# 433.net
KiCad netlist of a schematic drawn in EasyEDA Pro
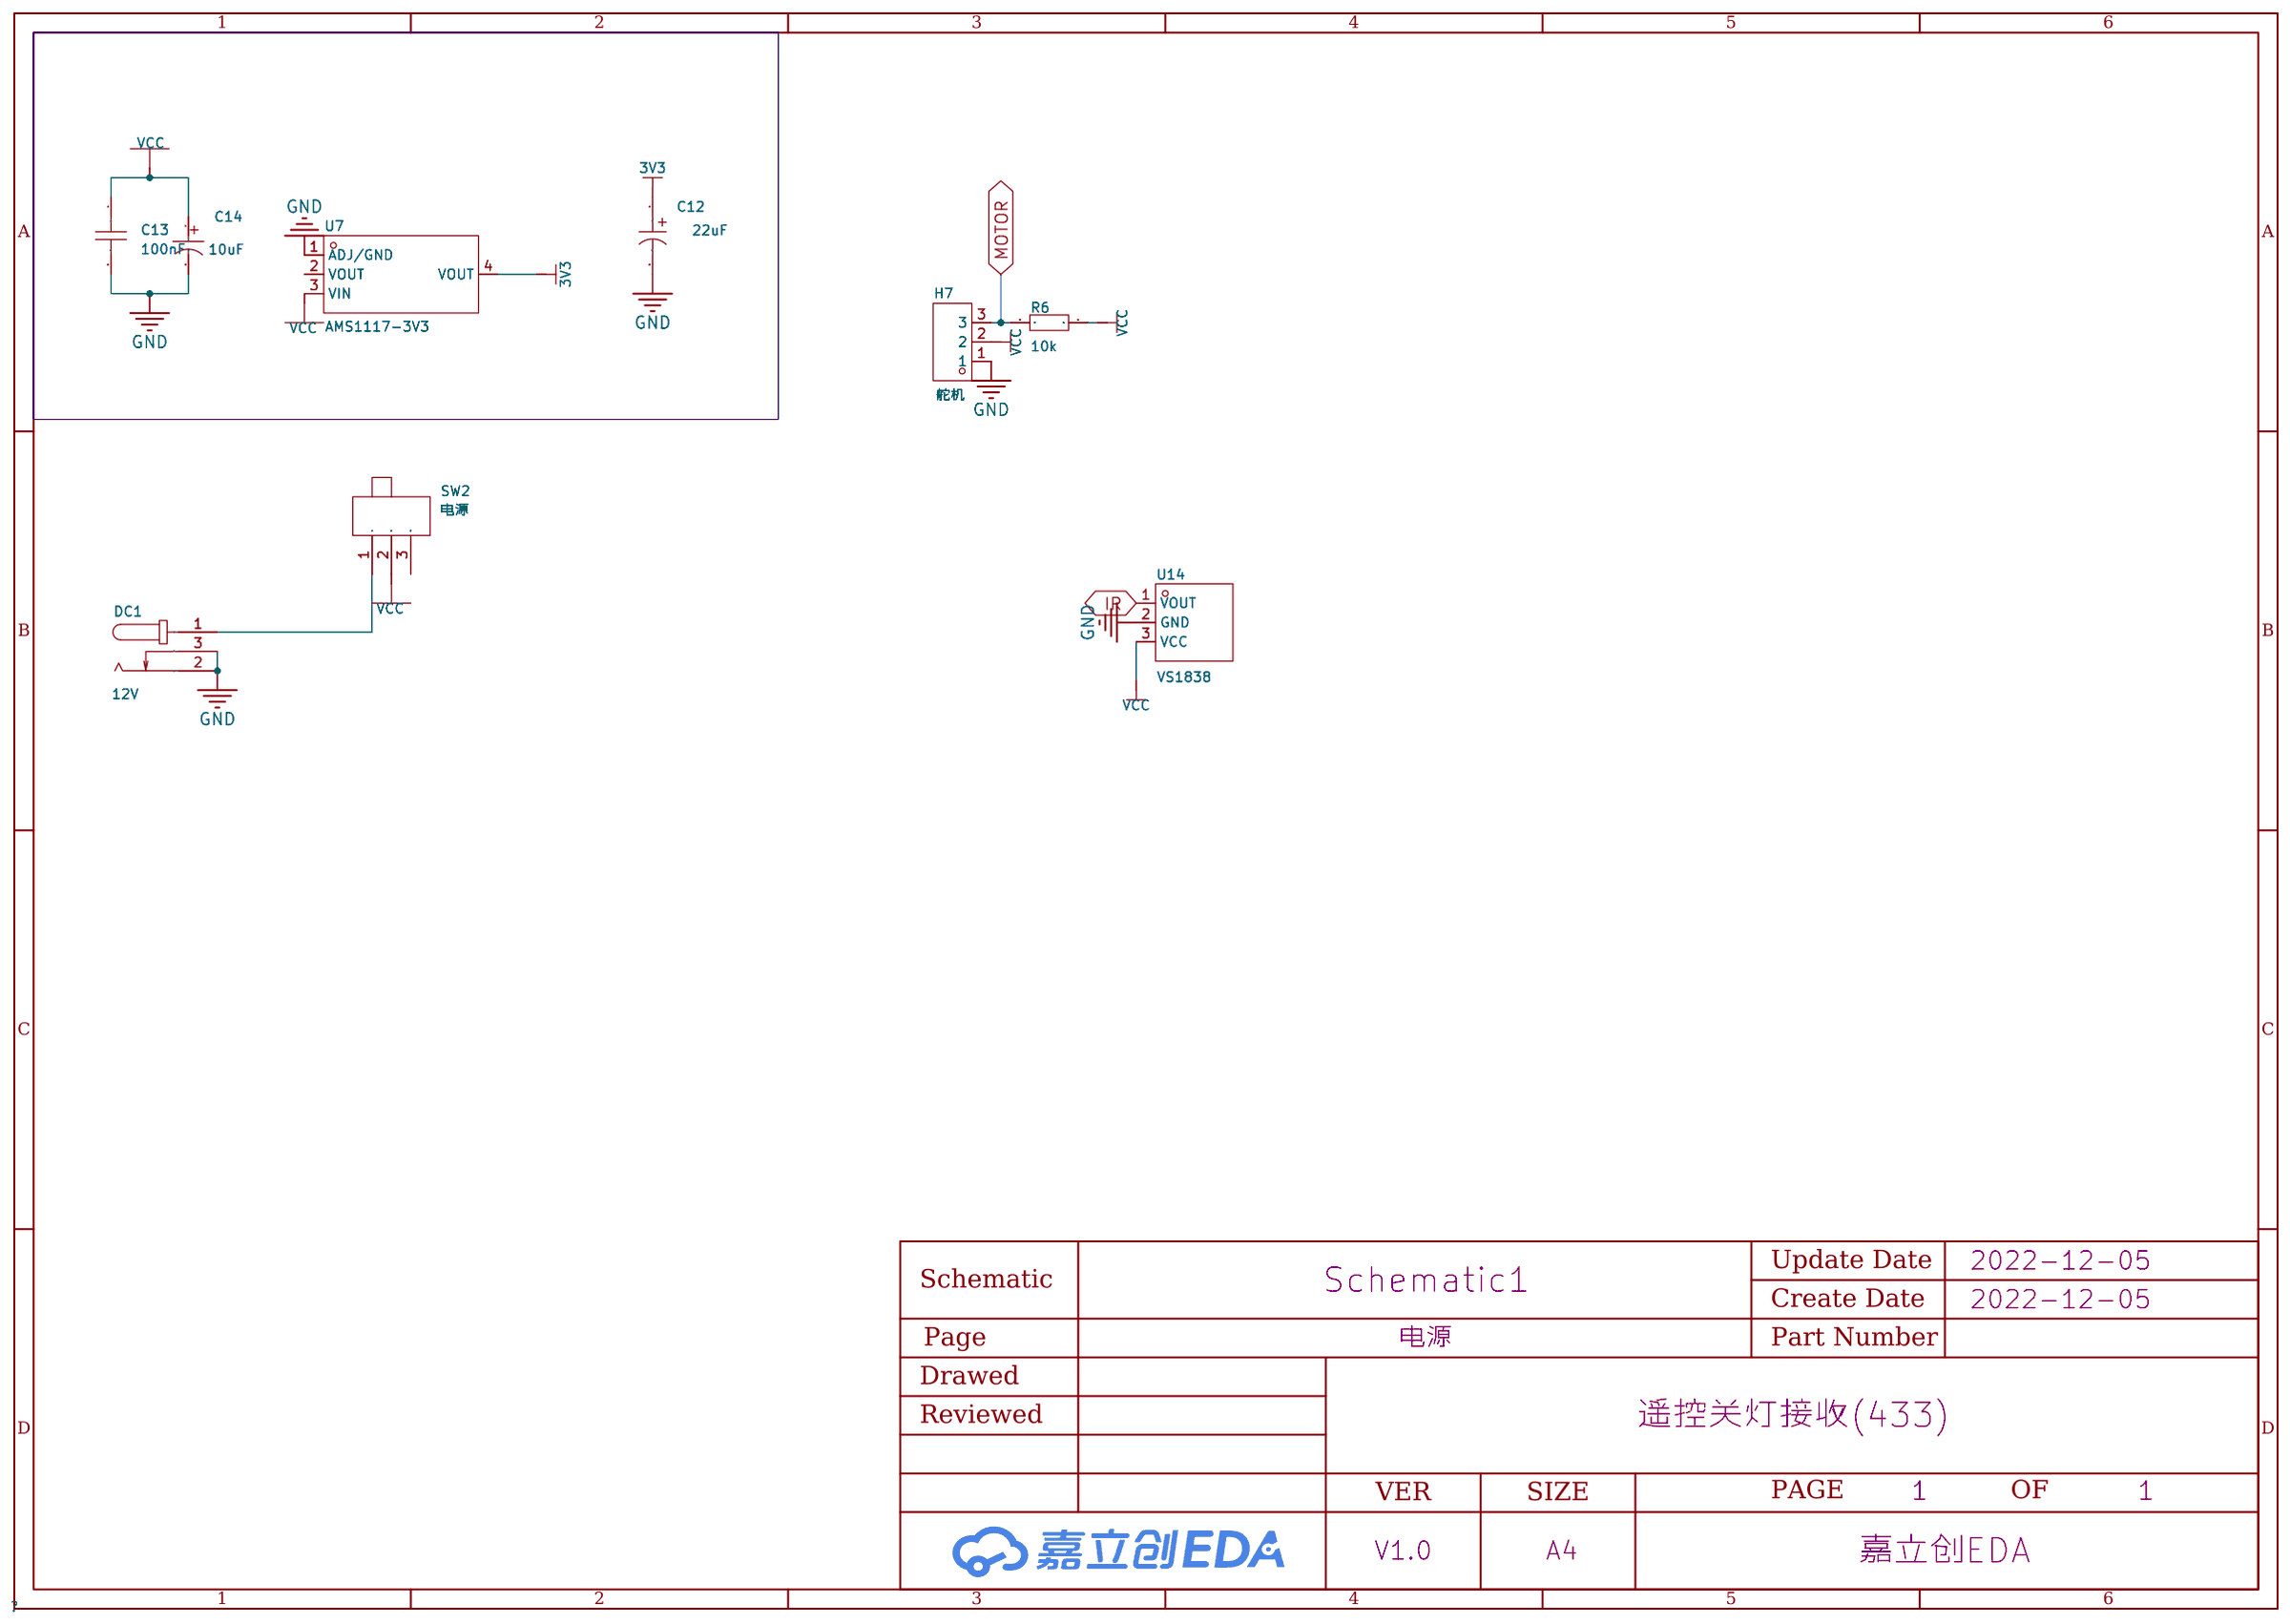
[diagram p0: 电源]
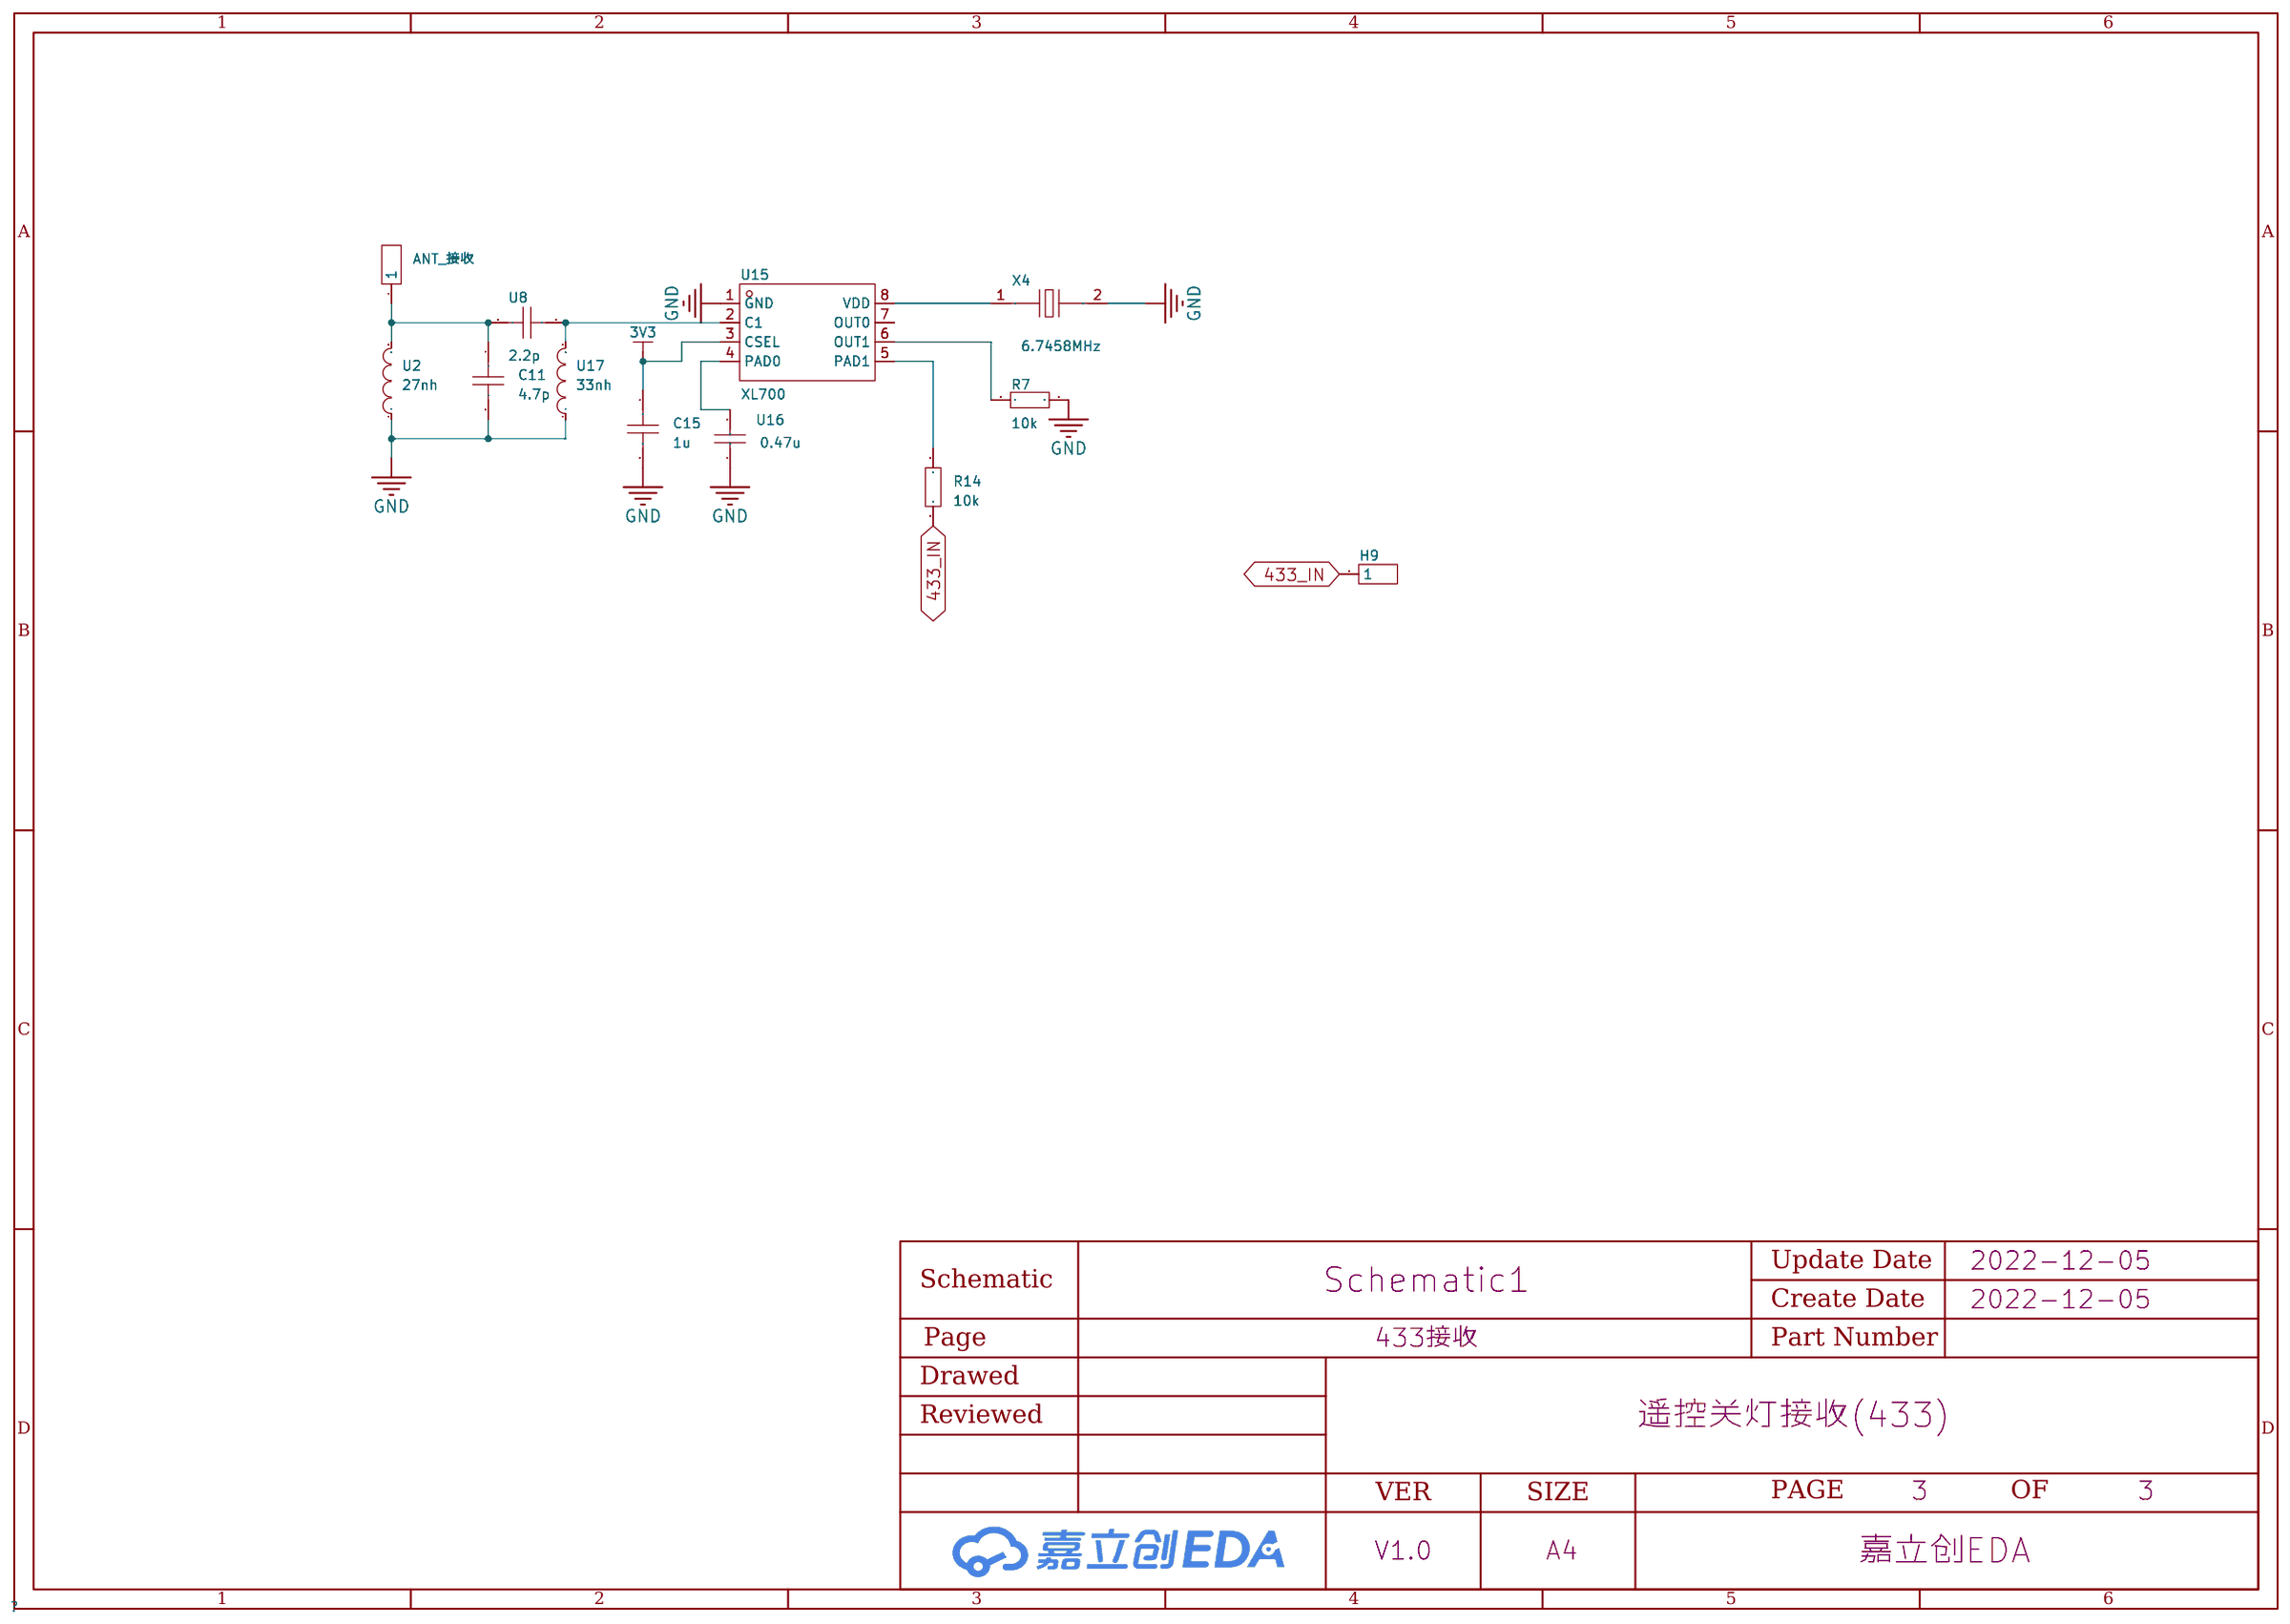
[diagram p1: 433接收]
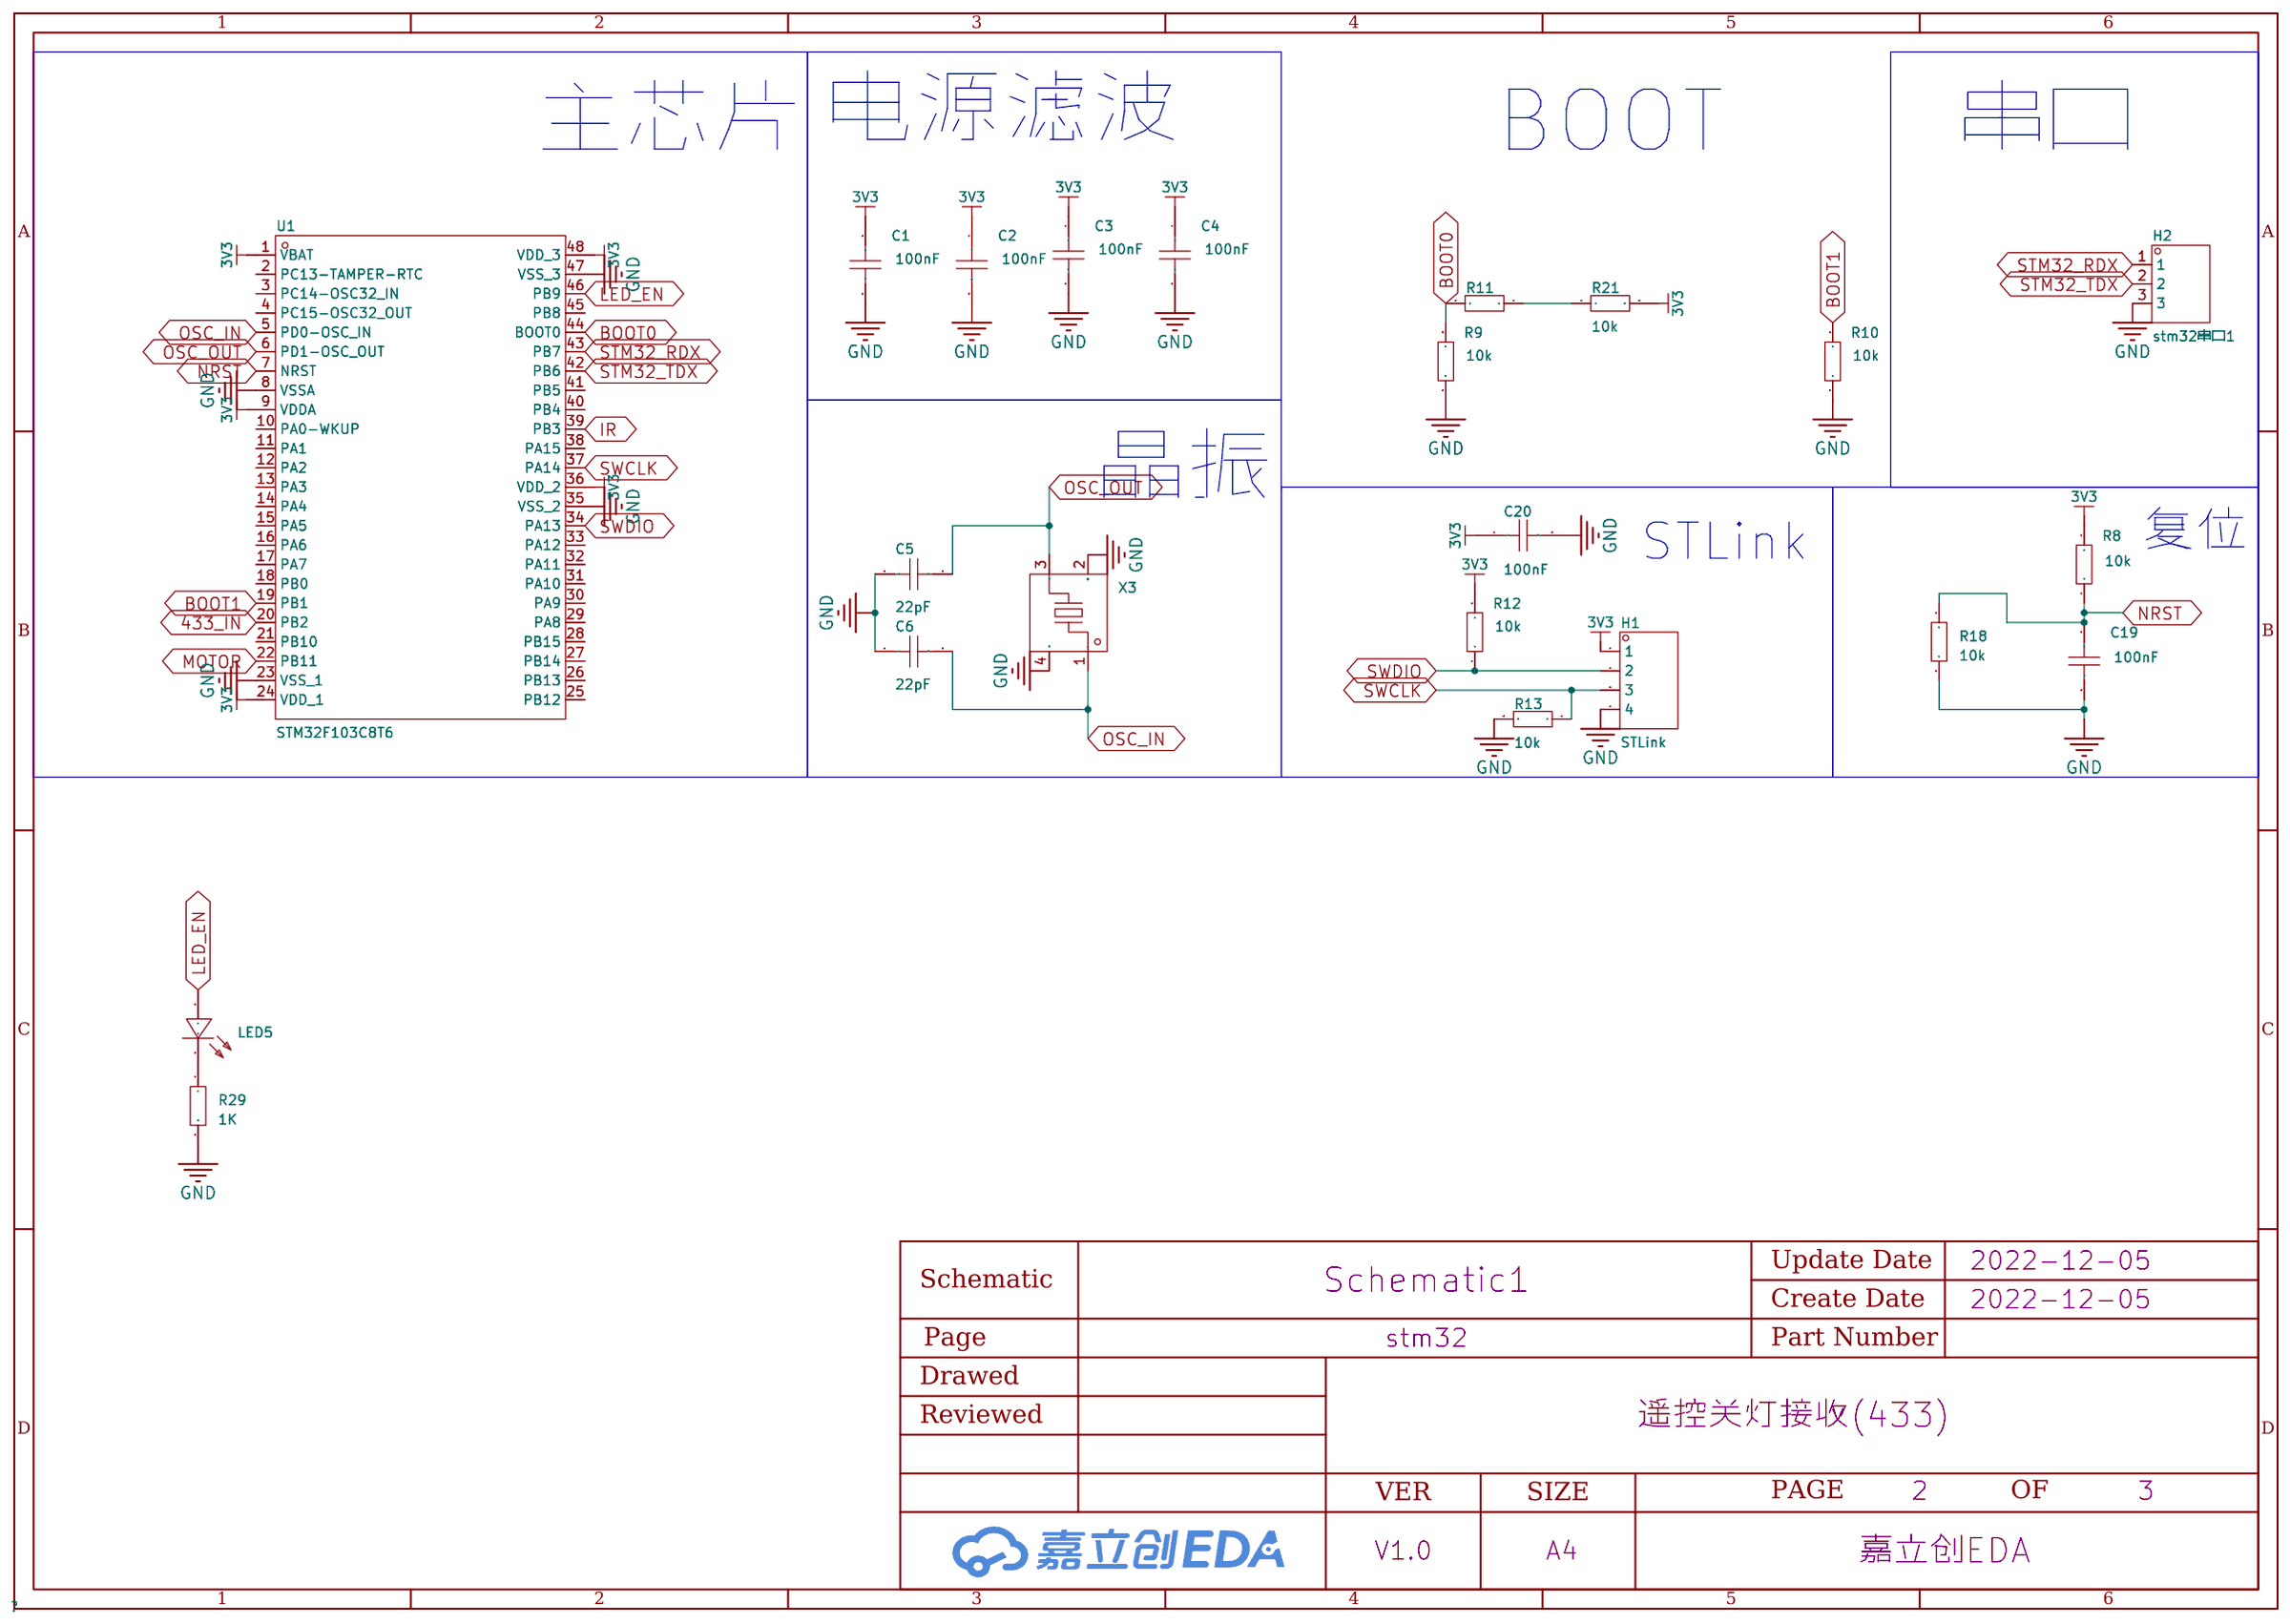
[diagram p2: stm32]

(export (version "E")
  (design (tool "Eeschema 10.0.6"))
  (components
    (comp (ref "C12")
      (value "22uF")
      (footprint "easyedapro:CAP-TH_BD5.0-P2.00-D0.6-FD")
      (fields
        (field (name "Manufacturer Part") "LW220M0500511PV2-D5")
        (field (name "Manufacturer") "UNITED(怡德)")
      )
      (libsource (lib "easyedapro") (part "LW220M0500511PV2-D5"))
    )
    (comp (ref "C13")
      (value "100nF")
      (footprint "easyedapro:C0805")
      (fields (field (name "Manufacturer Part") "0805"))
      (libsource (lib "easyedapro") (part "0805_C9900012713"))
    )
    (comp (ref "C14")
      (value "10uF")
      (footprint "easyedapro:CAP-TH_BD5.0-P2.00-D0.8-FD")
      (fields
        (field (name "Manufacturer Part") "KM106M025D11RR0VH2FP0")
        (field (name "Manufacturer") "CX(承兴)")
      )
      (libsource (lib "easyedapro") (part "10uF 25V 5*11"))
    )
    (comp (ref "DC1")
      (value "12V")
      (footprint "easyedapro:DC-IN-TH_DC005-T20")
      (description "连接器类型:DC电源插座;安装方式:弯插;触点内径:-;触点外径:6.3mm;额定电流:3A;额定电压:30V;工作温度范围:-10~+60;")
      (fields (field (name "Manufacturer Part") "DC005-T20") (field (name "Manufacturer") "SOFNG(硕方)"))
      (libsource (lib "easyedapro") (part "DC005-2.0MM"))
    )
    (comp (ref "H7")
      (value "舵机")
      (footprint "easyedapro:HDR-TH_3P-P2.54-V-F")
      (libsource (lib "easyedapro") (part "PM254V-11-03-H85"))
    )
    (comp (ref "R6")
      (value "10k")
      (footprint "easyedapro:R0805")
      (fields (field (name "Manufacturer Part") "0805"))
      (libsource (lib "easyedapro") (part "0805"))
    )
    (comp (ref "SW2")
      (value "电源")
      (footprint "easyedapro:SW-TH_MK-12D18-G040")
      (fields (field (name "Manufacturer Part") "MK-12D18-G020") (field (name "Manufacturer") "G-Switch(品赞)"))
      (libsource (lib "easyedapro") (part "MK-12D18-G020"))
    )
    (comp (ref "U7")
      (value "AMS1117-3V3")
      (footprint "easyedapro:SOT-223-3_L6.7-W3.7-P2.30-LS7.0-BR")
      (description "静态电流(Iq):-;输出类型:固定;最大输入电压:18V;输出电压(可调):-;压降(max):1.5V @ 1A;输出电压(固定):5V;")
      (fields (field (name "Manufacturer Part") "AMS1117-5.0") (field (name "Manufacturer") "Slkor(萨科微)"))
      (libsource (lib "easyedapro") (part "AMS1117-5.0_C473812"))
    )
    (comp (ref "U14")
      (value "VS1838")
      (footprint "easyedapro:OPTO-TH_3P-L7.0-W5.6-P2.54-L")
      (fields (field (name "Manufacturer Part") "DY-IRM-AC01-AN") (field (name "Manufacturer") "TONYU(东裕)"))
      (libsource (lib "easyedapro") (part "DY-IRM-AC01-AN"))
    )
    (comp (ref "ANT_接收")
      (value "~")
      (footprint "easyedapro:HDR-TH_1P-V-M_XKB_X4611WV-01I-C28D40")
      (libsource (lib "easyedapro") (part "HDR_1x1"))
    )
    (comp (ref "C11")
      (value "4.7p")
      (footprint "easyedapro:C0805")
      (fields (field (name "Manufacturer Part") "0805"))
      (libsource (lib "easyedapro") (part "0805_C9900012713"))
    )
    (comp (ref "C15")
      (value "1u")
      (footprint "easyedapro:C0805")
      (fields (field (name "Manufacturer Part") "0805"))
      (libsource (lib "easyedapro") (part "0805_C9900012713"))
    )
    (comp (ref "H9")
      (value "~")
      (footprint "easyedapro:HDR-TH_1P-V-M_XKB_X4611WV-01I-C28D40")
      (libsource (lib "easyedapro") (part "HDR_1x1"))
    )
    (comp (ref "R7")
      (value "10k")
      (footprint "easyedapro:R0805")
      (fields (field (name "Manufacturer Part") "0805"))
      (libsource (lib "easyedapro") (part "0805"))
    )
    (comp (ref "R14")
      (value "10k")
      (footprint "easyedapro:R0805")
      (fields (field (name "Manufacturer Part") "0805"))
      (libsource (lib "easyedapro") (part "0805"))
    )
    (comp (ref "U2")
      (value "27nh")
      (footprint "easyedapro:L0603")
      (fields (field (name "Manufacturer Part") "1.3nH±10%"))
      (libsource (lib "easyedapro") (part "1.3NH±10%"))
    )
    (comp (ref "U8")
      (value "2.2p")
      (footprint "easyedapro:C0603")
      (fields (field (name "Manufacturer Part") "104P"))
      (libsource (lib "easyedapro") (part "104P"))
    )
    (comp (ref "U15")
      (value "XL700")
      (footprint "easyedapro:SOP-8_L4.9-W3.9-P1.27-LS6.0-BL")
      (fields (field (name "Manufacturer Part") "XW02E SOP8") (field (name "Manufacturer") "Sam&wing(芯网)"))
      (libsource (lib "easyedapro") (part "XW02E SOP8"))
    )
    (comp (ref "U16")
      (value "0.47u")
      (footprint "easyedapro:C0402")
      (fields (field (name "Manufacturer Part") "16p"))
      (libsource (lib "easyedapro") (part "16P"))
    )
    (comp (ref "U17")
      (value "33nh")
      (footprint "easyedapro:L0603")
      (fields (field (name "Manufacturer Part") "1.3nH±10%"))
      (libsource (lib "easyedapro") (part "1.3NH±10%"))
    )
    (comp (ref "X4")
      (value "6.7458MHz")
      (footprint "easyedapro:OSC-SMD_2P-L11.4-W4.7-LS12.3")
      (description "晶振类型:-;频率:-;负载电容:-;工作温度:-;")
      (fields
        (field (name "Manufacturer Part") "49SMD-4MHZ-15PF-20PPM")
        (field (name "Manufacturer") "TKD(泰晶)")
      )
      (libsource (lib "easyedapro") (part "49SMD-4MHZ-15PF-20PPM"))
    )
    (comp (ref "C1")
      (value "100nF")
      (fields (field (name "Manufacturer Part") "0805"))
      (libsource (lib "easyedapro") (part "0805_C9900012713"))
    )
    (comp (ref "C2")
      (value "100nF")
      (fields (field (name "Manufacturer Part") "0805"))
      (libsource (lib "easyedapro") (part "0805_C9900012713"))
    )
    (comp (ref "C3")
      (value "100nF")
      (fields (field (name "Manufacturer Part") "0805"))
      (libsource (lib "easyedapro") (part "0805_C9900012713"))
    )
    (comp (ref "C4")
      (value "100nF")
      (fields (field (name "Manufacturer Part") "0805"))
      (libsource (lib "easyedapro") (part "0805_C9900012713"))
    )
    (comp (ref "C5")
      (value "22pF")
      (fields (field (name "Manufacturer Part") "0805"))
      (libsource (lib "easyedapro") (part "0805_C9900012713"))
    )
    (comp (ref "C6")
      (value "22pF")
      (fields (field (name "Manufacturer Part") "0805"))
      (libsource (lib "easyedapro") (part "0805_C9900012713"))
    )
    (comp (ref "C19")
      (value "100nF")
      (footprint "easyedapro:C0805")
      (fields (field (name "Manufacturer Part") "0805"))
      (libsource (lib "easyedapro") (part "0805_C9900012713"))
    )
    (comp (ref "C20")
      (value "100nF")
      (footprint "easyedapro:C0805")
      (fields (field (name "Manufacturer Part") "0805"))
      (libsource (lib "easyedapro") (part "0805_C9900012713"))
    )
    (comp (ref "H1")
      (value "STLink")
      (footprint "easyedapro:HDR-TH_4P-P2.54-V-M")
      (fields (field (name "Manufacturer Part") "B-2100S04P-A110") (field (name "Manufacturer") "Ckmtw(灿科盟)"))
      (libsource (lib "easyedapro") (part "Header-Male-2.54_1x4"))
    )
    (comp (ref "H2")
      (value "stm32串口1")
      (footprint "easyedapro:HDR-TH_3P-P2.54-V-M-1")
      (fields (field (name "Manufacturer Part") "77311-102-03LF") (field (name "Manufacturer") "Amphenol"))
      (libsource (lib "easyedapro") (part "77311-102-03LF"))
    )
    (comp (ref "LED5")
      (value "~")
      (footprint "easyedapro:LED0805-R-RD")
      (description "发光颜色:翠绿;")
      (fields (field (name "Manufacturer Part") "NCD0805G1") (field (name "Manufacturer") "国星光电"))
      (libsource (lib "easyedapro") (part "FC-2012UGK-520D5"))
    )
    (comp (ref "R8")
      (value "10k")
      (footprint "easyedapro:R0805")
      (fields (field (name "Manufacturer Part") "0805"))
      (libsource (lib "easyedapro") (part "0805"))
    )
    (comp (ref "R9")
      (value "10k")
      (footprint "easyedapro:R0805")
      (fields (field (name "Manufacturer Part") "0805"))
      (libsource (lib "easyedapro") (part "0805"))
    )
    (comp (ref "R10")
      (value "10k")
      (footprint "easyedapro:R0805")
      (fields (field (name "Manufacturer Part") "0805"))
      (libsource (lib "easyedapro") (part "0805"))
    )
    (comp (ref "R11")
      (value "100R")
      (footprint "easyedapro:R0805")
      (fields (field (name "Manufacturer Part") "0805"))
      (libsource (lib "easyedapro") (part "0805"))
    )
    (comp (ref "R12")
      (value "10k")
      (footprint "easyedapro:R0805")
      (fields (field (name "Manufacturer Part") "0805"))
      (libsource (lib "easyedapro") (part "0805"))
    )
    (comp (ref "R13")
      (value "10k")
      (footprint "easyedapro:R0805")
      (fields (field (name "Manufacturer Part") "0805"))
      (libsource (lib "easyedapro") (part "0805"))
    )
    (comp (ref "R18")
      (value "10k")
      (footprint "easyedapro:R0805")
      (fields (field (name "Manufacturer Part") "0805"))
      (libsource (lib "easyedapro") (part "0805"))
    )
    (comp (ref "R21")
      (value "10k")
      (footprint "easyedapro:R0805")
      (fields (field (name "Manufacturer Part") "0805"))
      (libsource (lib "easyedapro") (part "0805"))
    )
    (comp (ref "R29")
      (value "1K")
      (footprint "easyedapro:R0805")
      (fields (field (name "Manufacturer Part") "0805"))
      (libsource (lib "easyedapro") (part "0805"))
    )
    (comp (ref "U1")
      (value "STM32F103C8T6")
      (footprint "easyedapro:LQFP-48_L7.0-W7.0-P0.50-LS9.0-BL")
      (description "CPU位数:32-Bit;ROM类型:FLASH;CPU内核:ARM® Cortex®-M3;主频（MAX):72MHz;工作电压:2V ~ 3.6V;")
      (fields (field (name "Manufacturer") "ST(意法半导体)"))
      (libsource (lib "easyedapro") (part "STM32F103C8T6"))
    )
    (comp (ref "X3")
      (value "NX3225SA-26MHz-STD-CSR-6")
      (footprint "easyedapro:CRYSTAL-SMD_4P-L3.2-W2.5-BL")
      (fields (field (name "Manufacturer") "NDK"))
      (libsource (lib "easyedapro") (part "NX3225SA-26MHZ-STD-CSR-6"))
    )
  )
  (nets
    (net (code "1") (name "3V3") (class "Default")
      (node (ref "C1") (pin "1") (pinfunction "1_1") (pintype "input"))
      (node (ref "C12") (pin "1") (pinfunction "1_1") (pintype "input"))
      (node (ref "C15") (pin "1") (pinfunction "1_1") (pintype "input"))
      (node (ref "C2") (pin "1") (pinfunction "1_1") (pintype "input"))
      (node (ref "C20") (pin "1") (pinfunction "1_1") (pintype "input"))
      (node (ref "C3") (pin "1") (pinfunction "1_1") (pintype "input"))
      (node (ref "C4") (pin "1") (pinfunction "1_1") (pintype "input"))
      (node (ref "H1") (pin "1") (pinfunction "1_1") (pintype "input"))
      (node (ref "R12") (pin "2") (pinfunction "2_2") (pintype "input"))
      (node (ref "R21") (pin "2") (pinfunction "2_2") (pintype "input"))
      (node (ref "R8") (pin "2") (pinfunction "2_2") (pintype "input"))
      (node (ref "U1") (pin "1") (pinfunction "VBAT_1") (pintype "input"))
      (node (ref "U1") (pin "24") (pinfunction "VDD_1_24") (pintype "input"))
      (node (ref "U1") (pin "36") (pinfunction "VDD_2_36") (pintype "input"))
      (node (ref "U1") (pin "48") (pinfunction "VDD_3_48") (pintype "input"))
      (node (ref "U1") (pin "9") (pinfunction "VDDA_9") (pintype "input"))
      (node (ref "U15") (pin "3") (pinfunction "CSEL_3") (pintype "input"))
      (node (ref "U7") (pin "4") (pinfunction "VOUT_4") (pintype "input"))
    )
    (net (code "2") (name "433_IN") (class "Default")
      (node (ref "H9") (pin "1") (pinfunction "1_1") (pintype "unspecified"))
      (node (ref "R14") (pin "2") (pinfunction "2_2") (pintype "input"))
      (node (ref "U1") (pin "20") (pinfunction "PB2_20") (pintype "input"))
    )
    (net (code "3") (name "BOOT0") (class "Default")
      (node (ref "R11") (pin "2") (pinfunction "2_2") (pintype "input"))
      (node (ref "R9") (pin "2") (pinfunction "2_2") (pintype "input"))
      (node (ref "U1") (pin "44") (pinfunction "BOOT0_44") (pintype "input"))
    )
    (net (code "4") (name "BOOT1") (class "Default")
      (node (ref "R10") (pin "2") (pinfunction "2_2") (pintype "input"))
      (node (ref "U1") (pin "19") (pinfunction "PB1_19") (pintype "input"))
    )
    (net (code "5") (name "GND") (class "Default")
      (node (ref "C1") (pin "2") (pinfunction "2_2") (pintype "input"))
      (node (ref "C11") (pin "2") (pinfunction "2_2") (pintype "input"))
      (node (ref "C12") (pin "2") (pinfunction "2_2") (pintype "input"))
      (node (ref "C13") (pin "2") (pinfunction "2_2") (pintype "input"))
      (node (ref "C14") (pin "2") (pinfunction "2_2") (pintype "input"))
      (node (ref "C15") (pin "2") (pinfunction "2_2") (pintype "input"))
      (node (ref "C19") (pin "2") (pinfunction "2_2") (pintype "input"))
      (node (ref "C2") (pin "2") (pinfunction "2_2") (pintype "input"))
      (node (ref "C20") (pin "2") (pinfunction "2_2") (pintype "input"))
      (node (ref "C3") (pin "2") (pinfunction "2_2") (pintype "input"))
      (node (ref "C4") (pin "2") (pinfunction "2_2") (pintype "input"))
      (node (ref "C5") (pin "1") (pinfunction "1_1") (pintype "input"))
      (node (ref "C6") (pin "1") (pinfunction "1_1") (pintype "input"))
      (node (ref "DC1") (pin "2") (pinfunction "2_2") (pintype "input"))
      (node (ref "DC1") (pin "3") (pinfunction "3_3") (pintype "input"))
      (node (ref "H1") (pin "4") (pinfunction "4_4") (pintype "input"))
      (node (ref "H2") (pin "3") (pinfunction "3_3") (pintype "input"))
      (node (ref "H7") (pin "1") (pinfunction "1_1") (pintype "input"))
      (node (ref "R10") (pin "1") (pinfunction "1_1") (pintype "input"))
      (node (ref "R13") (pin "2") (pinfunction "2_2") (pintype "input"))
      (node (ref "R18") (pin "2") (pinfunction "2_2") (pintype "input"))
      (node (ref "R29") (pin "2") (pinfunction "2_2") (pintype "input"))
      (node (ref "R7") (pin "1") (pinfunction "1_1") (pintype "input"))
      (node (ref "R9") (pin "1") (pinfunction "1_1") (pintype "input"))
      (node (ref "U1") (pin "23") (pinfunction "VSS_1_23") (pintype "input"))
      (node (ref "U1") (pin "35") (pinfunction "VSS_2_35") (pintype "input"))
      (node (ref "U1") (pin "47") (pinfunction "VSS_3_47") (pintype "input"))
      (node (ref "U1") (pin "8") (pinfunction "VSSA_8") (pintype "input"))
      (node (ref "U14") (pin "2") (pinfunction "GND_2") (pintype "input"))
      (node (ref "U15") (pin "1") (pinfunction "GND_1") (pintype "input"))
      (node (ref "U16") (pin "1") (pinfunction "1_1") (pintype "input"))
      (node (ref "U17") (pin "1") (pinfunction "1_1") (pintype "input"))
      (node (ref "U2") (pin "1") (pinfunction "1_1") (pintype "input"))
      (node (ref "U7") (pin "1") (pinfunction "ADJ/GND_1") (pintype "input"))
      (node (ref "X3") (pin "2") (pinfunction "GND_2") (pintype "input"))
      (node (ref "X3") (pin "4") (pinfunction "GND_4") (pintype "input"))
      (node (ref "X4") (pin "2") (pinfunction "2_2") (pintype "input"))
    )
    (net (code "6") (name "IR") (class "Default")
      (node (ref "U1") (pin "39") (pinfunction "PB3_39") (pintype "input"))
      (node (ref "U14") (pin "1") (pinfunction "VOUT_1") (pintype "input"))
    )
    (net (code "7") (name "LED_EN") (class "Default")
      (node (ref "LED5") (pin "1") (pinfunction "A_1") (pintype "input"))
      (node (ref "U1") (pin "46") (pinfunction "PB9_46") (pintype "input"))
    )
    (net (code "8") (name "MOTOR") (class "Default")
      (node (ref "H7") (pin "3") (pinfunction "3_3") (pintype "input"))
      (node (ref "R6") (pin "2") (pinfunction "2_2") (pintype "input"))
      (node (ref "U1") (pin "22") (pinfunction "PB11_22") (pintype "input"))
    )
    (net (code "9") (name "NRST") (class "Default")
      (node (ref "C19") (pin "1") (pinfunction "1_1") (pintype "input"))
      (node (ref "R18") (pin "1") (pinfunction "1_1") (pintype "input"))
      (node (ref "R8") (pin "1") (pinfunction "1_1") (pintype "input"))
      (node (ref "U1") (pin "7") (pinfunction "NRST_7") (pintype "input"))
    )
    (net (code "10") (name "Net-(ANT_接收-Pad1)") (class "Default")
      (node (ref "ANT_接收") (pin "1") (pinfunction "1_1") (pintype "unspecified"))
      (node (ref "C11") (pin "1") (pinfunction "1_1") (pintype "input"))
      (node (ref "U2") (pin "2") (pinfunction "2_2") (pintype "input"))
      (node (ref "U8") (pin "2") (pinfunction "2_2") (pintype "input"))
    )
    (net (code "11") (name "Net-(DC1-Pad1)") (class "Default")
      (node (ref "DC1") (pin "1") (pinfunction "1_1") (pintype "input"))
      (node (ref "SW2") (pin "1") (pinfunction "1_1") (pintype "input"))
    )
    (net (code "12") (name "Net-(LED5-K)") (class "Default")
      (node (ref "LED5") (pin "2") (pinfunction "K_2") (pintype "input"))
      (node (ref "R29") (pin "1") (pinfunction "1_1") (pintype "input"))
    )
    (net (code "13") (name "Net-(R11-Pad1)") (class "Default")
      (node (ref "R11") (pin "1") (pinfunction "1_1") (pintype "input"))
      (node (ref "R21") (pin "1") (pinfunction "1_1") (pintype "input"))
    )
    (net (code "14") (name "Net-(U15-C1)") (class "Default")
      (node (ref "U15") (pin "2") (pinfunction "C1_2") (pintype "input"))
      (node (ref "U17") (pin "2") (pinfunction "2_2") (pintype "input"))
      (node (ref "U8") (pin "1") (pinfunction "1_1") (pintype "input"))
    )
    (net (code "15") (name "Net-(U15-OUT1)") (class "Default")
      (node (ref "R7") (pin "2") (pinfunction "2_2") (pintype "input"))
      (node (ref "U15") (pin "6") (pinfunction "OUT1_6") (pintype "input"))
    )
    (net (code "16") (name "Net-(U15-PAD0)") (class "Default")
      (node (ref "U15") (pin "4") (pinfunction "PAD0_4") (pintype "input"))
      (node (ref "U16") (pin "2") (pinfunction "2_2") (pintype "input"))
    )
    (net (code "17") (name "Net-(U15-PAD1)") (class "Default")
      (node (ref "R14") (pin "1") (pinfunction "1_1") (pintype "input"))
      (node (ref "U15") (pin "5") (pinfunction "PAD1_5") (pintype "input"))
    )
    (net (code "18") (name "Net-(U15-VDD)") (class "Default")
      (node (ref "U15") (pin "8") (pinfunction "VDD_8") (pintype "input"))
      (node (ref "X4") (pin "1") (pinfunction "1_1") (pintype "input"))
    )
    (net (code "19") (name "OSC_IN") (class "Default")
      (node (ref "C6") (pin "2") (pinfunction "2_2") (pintype "input"))
      (node (ref "U1") (pin "5") (pinfunction "PD0-OSC_IN_5") (pintype "input"))
      (node (ref "X3") (pin "1") (pinfunction "1_1") (pintype "input"))
    )
    (net (code "20") (name "OSC_OUT") (class "Default")
      (node (ref "C5") (pin "2") (pinfunction "2_2") (pintype "input"))
      (node (ref "U1") (pin "6") (pinfunction "PD1-OSC_OUT_6") (pintype "input"))
      (node (ref "X3") (pin "3") (pinfunction "3_3") (pintype "input"))
    )
    (net (code "21") (name "STM32_RDX") (class "Default")
      (node (ref "H2") (pin "1") (pinfunction "1_1") (pintype "input"))
      (node (ref "U1") (pin "43") (pinfunction "PB7_43") (pintype "input"))
    )
    (net (code "22") (name "STM32_TDX") (class "Default")
      (node (ref "H2") (pin "2") (pinfunction "2_2") (pintype "input"))
      (node (ref "U1") (pin "42") (pinfunction "PB6_42") (pintype "input"))
    )
    (net (code "23") (name "SWCLK") (class "Default")
      (node (ref "H1") (pin "3") (pinfunction "3_3") (pintype "input"))
      (node (ref "R13") (pin "1") (pinfunction "1_1") (pintype "input"))
      (node (ref "U1") (pin "37") (pinfunction "PA14_37") (pintype "input"))
    )
    (net (code "24") (name "SWDIO") (class "Default")
      (node (ref "H1") (pin "2") (pinfunction "2_2") (pintype "input"))
      (node (ref "R12") (pin "1") (pinfunction "1_1") (pintype "input"))
      (node (ref "U1") (pin "34") (pinfunction "PA13_34") (pintype "input"))
    )
    (net (code "25") (name "VCC") (class "Default")
      (node (ref "C13") (pin "1") (pinfunction "1_1") (pintype "input"))
      (node (ref "C14") (pin "1") (pinfunction "1_1") (pintype "input"))
      (node (ref "H7") (pin "2") (pinfunction "2_2") (pintype "input"))
      (node (ref "R6") (pin "1") (pinfunction "1_1") (pintype "input"))
      (node (ref "SW2") (pin "2") (pinfunction "2_2") (pintype "input"))
      (node (ref "U14") (pin "3") (pinfunction "VCC_3") (pintype "input"))
      (node (ref "U7") (pin "3") (pinfunction "VIN_3") (pintype "input"))
    )
    (net (code "26") (name "unconnected-(SW2-Pad3)") (class "Default")
      (node (ref "SW2") (pin "3") (pinfunction "3_3") (pintype "input"))
    )
    (net (code "27") (name "unconnected-(U1-PA0-WKUP-Pad10)") (class "Default")
      (node (ref "U1") (pin "10") (pinfunction "PA0-WKUP_10") (pintype "input"))
    )
    (net (code "28") (name "unconnected-(U1-PA1-Pad11)") (class "Default")
      (node (ref "U1") (pin "11") (pinfunction "PA1_11") (pintype "input"))
    )
    (net (code "29") (name "unconnected-(U1-PA2-Pad12)") (class "Default")
      (node (ref "U1") (pin "12") (pinfunction "PA2_12") (pintype "input"))
    )
    (net (code "30") (name "unconnected-(U1-PA3-Pad13)") (class "Default")
      (node (ref "U1") (pin "13") (pinfunction "PA3_13") (pintype "input"))
    )
    (net (code "31") (name "unconnected-(U1-PA4-Pad14)") (class "Default")
      (node (ref "U1") (pin "14") (pinfunction "PA4_14") (pintype "input"))
    )
    (net (code "32") (name "unconnected-(U1-PA5-Pad15)") (class "Default")
      (node (ref "U1") (pin "15") (pinfunction "PA5_15") (pintype "input"))
    )
    (net (code "33") (name "unconnected-(U1-PA6-Pad16)") (class "Default")
      (node (ref "U1") (pin "16") (pinfunction "PA6_16") (pintype "input"))
    )
    (net (code "34") (name "unconnected-(U1-PA7-Pad17)") (class "Default")
      (node (ref "U1") (pin "17") (pinfunction "PA7_17") (pintype "input"))
    )
    (net (code "35") (name "unconnected-(U1-PA8-Pad29)") (class "Default")
      (node (ref "U1") (pin "29") (pinfunction "PA8_29") (pintype "input"))
    )
    (net (code "36") (name "unconnected-(U1-PA9-Pad30)") (class "Default")
      (node (ref "U1") (pin "30") (pinfunction "PA9_30") (pintype "input"))
    )
    (net (code "37") (name "unconnected-(U1-PA10-Pad31)") (class "Default")
      (node (ref "U1") (pin "31") (pinfunction "PA10_31") (pintype "input"))
    )
    (net (code "38") (name "unconnected-(U1-PA11-Pad32)") (class "Default")
      (node (ref "U1") (pin "32") (pinfunction "PA11_32") (pintype "input"))
    )
    (net (code "39") (name "unconnected-(U1-PA12-Pad33)") (class "Default")
      (node (ref "U1") (pin "33") (pinfunction "PA12_33") (pintype "input"))
    )
    (net (code "40") (name "unconnected-(U1-PA15-Pad38)") (class "Default")
      (node (ref "U1") (pin "38") (pinfunction "PA15_38") (pintype "input"))
    )
    (net (code "41") (name "unconnected-(U1-PB0-Pad18)") (class "Default")
      (node (ref "U1") (pin "18") (pinfunction "PB0_18") (pintype "input"))
    )
    (net (code "42") (name "unconnected-(U1-PB4-Pad40)") (class "Default")
      (node (ref "U1") (pin "40") (pinfunction "PB4_40") (pintype "input"))
    )
    (net (code "43") (name "unconnected-(U1-PB5-Pad41)") (class "Default")
      (node (ref "U1") (pin "41") (pinfunction "PB5_41") (pintype "input"))
    )
    (net (code "44") (name "unconnected-(U1-PB8-Pad45)") (class "Default")
      (node (ref "U1") (pin "45") (pinfunction "PB8_45") (pintype "input"))
    )
    (net (code "45") (name "unconnected-(U1-PB10-Pad21)") (class "Default")
      (node (ref "U1") (pin "21") (pinfunction "PB10_21") (pintype "input"))
    )
    (net (code "46") (name "unconnected-(U1-PB12-Pad25)") (class "Default")
      (node (ref "U1") (pin "25") (pinfunction "PB12_25") (pintype "input"))
    )
    (net (code "47") (name "unconnected-(U1-PB13-Pad26)") (class "Default")
      (node (ref "U1") (pin "26") (pinfunction "PB13_26") (pintype "input"))
    )
    (net (code "48") (name "unconnected-(U1-PB14-Pad27)") (class "Default")
      (node (ref "U1") (pin "27") (pinfunction "PB14_27") (pintype "input"))
    )
    (net (code "49") (name "unconnected-(U1-PB15-Pad28)") (class "Default")
      (node (ref "U1") (pin "28") (pinfunction "PB15_28") (pintype "input"))
    )
    (net (code "50") (name "unconnected-(U1-PC13-TAMPER-RTC-Pad2)") (class "Default")
      (node (ref "U1") (pin "2") (pinfunction "PC13-TAMPER-RTC_2") (pintype "input"))
    )
    (net (code "51") (name "unconnected-(U1-PC14-OSC32_IN-Pad3)") (class "Default")
      (node (ref "U1") (pin "3") (pinfunction "PC14-OSC32_IN_3") (pintype "input"))
    )
    (net (code "52") (name "unconnected-(U1-PC15-OSC32_OUT-Pad4)") (class "Default")
      (node (ref "U1") (pin "4") (pinfunction "PC15-OSC32_OUT_4") (pintype "input"))
    )
    (net (code "53") (name "unconnected-(U7-VOUT-Pad2)") (class "Default")
      (node (ref "U7") (pin "2") (pinfunction "VOUT_2") (pintype "input"))
    )
    (net (code "54") (name "unconnected-(U15-OUT0-Pad7)") (class "Default")
      (node (ref "U15") (pin "7") (pinfunction "OUT0_7") (pintype "input"))
    )
  )
)
